# TapClip_v2.net
KiCad netlist of a schematic drawn in EAGLE
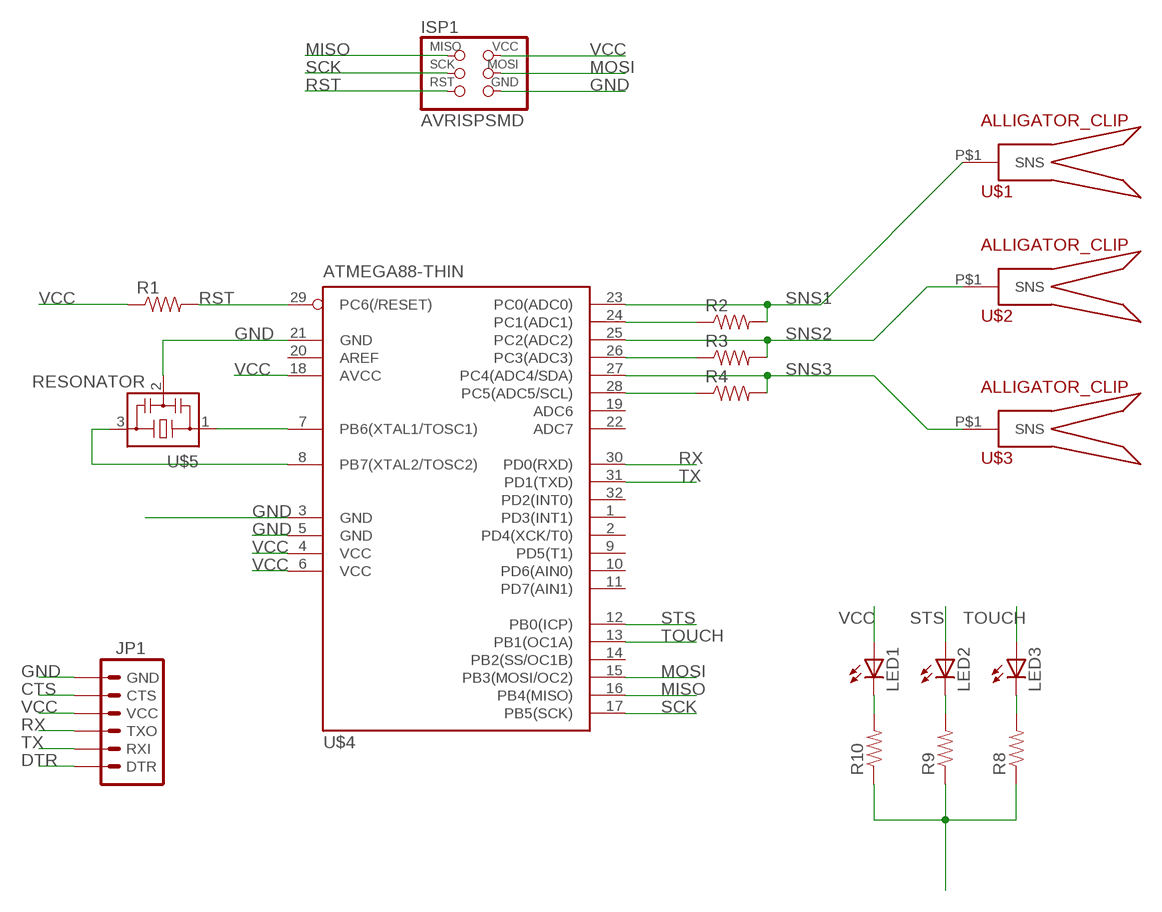
[diagram p0: schematic, sheet 1]

(export (version "E")
  (design (tool "Eeschema 10.0.6"))
  (components
    (comp (ref "ISP1")
      (value "AVRISPSMD")
      (footprint "eagle-import:2X03SMD")
      (libsource (lib "eagle-import") (part "AVRISPSMD"))
    )
    (comp (ref "JP1")
      (value "ARDUINO_SERIAL_PROGRAMSMD")
      (footprint "eagle-import:1X06-SMD")
      (libsource (lib "eagle-import") (part "ARDUINO_SERIAL_PROGRAMSMD"))
    )
    (comp (ref "LED1")
      (value "LED1206")
      (footprint "eagle-import:LED-1206")
      (libsource (lib "eagle-import") (part "LED1206"))
    )
    (comp (ref "LED2")
      (value "LED1206")
      (footprint "eagle-import:LED-1206")
      (libsource (lib "eagle-import") (part "LED1206"))
    )
    (comp (ref "LED3")
      (value "LED1206")
      (footprint "eagle-import:LED-1206")
      (libsource (lib "eagle-import") (part "LED1206"))
    )
    (comp (ref "R1")
      (value "RESISTOR0603-RES")
      (footprint "eagle-import:0603-RES")
      (libsource (lib "eagle-import") (part "RESISTOR0603-RES"))
    )
    (comp (ref "R2")
      (value "RESISTOR0603-RES")
      (footprint "eagle-import:0603-RES")
      (libsource (lib "eagle-import") (part "RESISTOR0603-RES"))
    )
    (comp (ref "R3")
      (value "RESISTOR0603-RES")
      (footprint "eagle-import:0603-RES")
      (libsource (lib "eagle-import") (part "RESISTOR0603-RES"))
    )
    (comp (ref "R4")
      (value "RESISTOR0603-RES")
      (footprint "eagle-import:0603-RES")
      (libsource (lib "eagle-import") (part "RESISTOR0603-RES"))
    )
    (comp (ref "R8")
      (value "RESISTOR1206")
      (footprint "eagle-import:1206")
      (libsource (lib "eagle-import") (part "RESISTOR1206"))
    )
    (comp (ref "R9")
      (value "RESISTOR1206")
      (footprint "eagle-import:1206")
      (libsource (lib "eagle-import") (part "RESISTOR1206"))
    )
    (comp (ref "R10")
      (value "RESISTOR1206")
      (footprint "eagle-import:1206")
      (libsource (lib "eagle-import") (part "RESISTOR1206"))
    )
    (comp (ref "U$1")
      (value "ALLIGATOR_CLIP")
      (footprint "eagle-import:ALLIGATOR_CLIP")
      (libsource (lib "eagle-import") (part "ALLIGATOR_CLIP"))
    )
    (comp (ref "U$2")
      (value "ALLIGATOR_CLIP")
      (footprint "eagle-import:ALLIGATOR_CLIP")
      (libsource (lib "eagle-import") (part "ALLIGATOR_CLIP"))
    )
    (comp (ref "U$3")
      (value "ALLIGATOR_CLIP")
      (footprint "eagle-import:ALLIGATOR_CLIP")
      (libsource (lib "eagle-import") (part "ALLIGATOR_CLIP"))
    )
    (comp (ref "U$4")
      (value "ATMEGA88-THIN")
      (footprint "eagle-import:TQFP32-08THIN")
      (libsource (lib "eagle-import") (part "ATMEGA88-THIN"))
    )
    (comp (ref "U$5")
      (value "RESONATOR")
      (footprint "eagle-import:EFOBM")
      (libsource (lib "eagle-import") (part "RESONATOR"))
    )
  )
  (nets
    (net (code "1") (name "/CTS") (class "Default")
      (node (ref "JP1") (pin "5") (pinfunction "CTS_5") (pintype "passive"))
    )
    (net (code "2") (name "/DTR") (class "Default")
      (node (ref "JP1") (pin "1") (pinfunction "DTR_1") (pintype "passive"))
    )
    (net (code "3") (name "/GND") (class "Default")
      (node (ref "ISP1") (pin "6") (pinfunction "GND_6") (pintype "passive"))
      (node (ref "JP1") (pin "6") (pinfunction "GND_6") (pintype "passive"))
      (node (ref "R10") (pin "1") (pinfunction "1_1") (pintype "passive"))
      (node (ref "R8") (pin "1") (pinfunction "1_1") (pintype "passive"))
      (node (ref "R9") (pin "1") (pinfunction "1_1") (pintype "passive"))
      (node (ref "U$4") (pin "21") (pinfunction "GND_21") (pintype "power_in"))
      (node (ref "U$4") (pin "3") (pinfunction "GND_3") (pintype "power_in"))
      (node (ref "U$4") (pin "5") (pinfunction "GND_5") (pintype "power_in"))
      (node (ref "U$5") (pin "2") (pinfunction "2_2") (pintype "passive"))
    )
    (net (code "4") (name "/MISO") (class "Default")
      (node (ref "ISP1") (pin "1") (pinfunction "MISO_1") (pintype "passive"))
      (node (ref "U$4") (pin "16") (pinfunction "PB4(MISO)_16") (pintype "bidirectional"))
    )
    (net (code "5") (name "/MOSI") (class "Default")
      (node (ref "ISP1") (pin "4") (pinfunction "MOSI_4") (pintype "passive"))
      (node (ref "U$4") (pin "15") (pinfunction "PB3(MOSI/OC2)_15") (pintype "bidirectional"))
    )
    (net (code "6") (name "/RST") (class "Default")
      (node (ref "ISP1") (pin "5") (pinfunction "RST_5") (pintype "passive"))
      (node (ref "R1") (pin "2") (pinfunction "2_2") (pintype "passive"))
      (node (ref "U$4") (pin "29") (pinfunction "PC6(/RESET)_29") (pintype "bidirectional"))
    )
    (net (code "7") (name "/RX") (class "Default")
      (node (ref "JP1") (pin "3") (pinfunction "TXO_3") (pintype "passive"))
      (node (ref "U$4") (pin "30") (pinfunction "PD0(RXD)_30") (pintype "bidirectional"))
    )
    (net (code "8") (name "/SCK") (class "Default")
      (node (ref "ISP1") (pin "3") (pinfunction "SCK_3") (pintype "passive"))
      (node (ref "U$4") (pin "17") (pinfunction "PB5(SCK)_17") (pintype "bidirectional"))
    )
    (net (code "9") (name "/SNS1") (class "Default")
      (node (ref "R2") (pin "2") (pinfunction "2_2") (pintype "passive"))
      (node (ref "U$1") (pin "P$1") (pinfunction "SNS_P$1") (pintype "bidirectional"))
      (node (ref "U$4") (pin "23") (pinfunction "PC0(ADC0)_23") (pintype "bidirectional"))
    )
    (net (code "10") (name "/SNS2") (class "Default")
      (node (ref "R3") (pin "2") (pinfunction "2_2") (pintype "passive"))
      (node (ref "U$2") (pin "P$1") (pinfunction "SNS_P$1") (pintype "bidirectional"))
      (node (ref "U$4") (pin "25") (pinfunction "PC2(ADC2)_25") (pintype "bidirectional"))
    )
    (net (code "11") (name "/SNS3") (class "Default")
      (node (ref "R4") (pin "2") (pinfunction "2_2") (pintype "passive"))
      (node (ref "U$3") (pin "P$1") (pinfunction "SNS_P$1") (pintype "bidirectional"))
      (node (ref "U$4") (pin "27") (pinfunction "PC4(ADC4/SDA)_27") (pintype "bidirectional"))
    )
    (net (code "12") (name "/STS") (class "Default")
      (node (ref "LED2") (pin "A") (pinfunction "A_A") (pintype "passive"))
      (node (ref "U$4") (pin "12") (pinfunction "PB0(ICP)_12") (pintype "bidirectional"))
    )
    (net (code "13") (name "/TOUCH") (class "Default")
      (node (ref "LED3") (pin "A") (pinfunction "A_A") (pintype "passive"))
      (node (ref "U$4") (pin "13") (pinfunction "PB1(OC1A)_13") (pintype "bidirectional"))
    )
    (net (code "14") (name "/TX") (class "Default")
      (node (ref "JP1") (pin "2") (pinfunction "RXI_2") (pintype "passive"))
      (node (ref "U$4") (pin "31") (pinfunction "PD1(TXD)_31") (pintype "bidirectional"))
    )
    (net (code "15") (name "/VCC") (class "Default")
      (node (ref "ISP1") (pin "2") (pinfunction "VCC_2") (pintype "passive"))
      (node (ref "JP1") (pin "4") (pinfunction "VCC_4") (pintype "passive"))
      (node (ref "LED1") (pin "A") (pinfunction "A_A") (pintype "passive"))
      (node (ref "R1") (pin "1") (pinfunction "1_1") (pintype "passive"))
      (node (ref "U$4") (pin "18") (pinfunction "AVCC_18") (pintype "power_in"))
      (node (ref "U$4") (pin "4") (pinfunction "VCC_4") (pintype "power_in"))
      (node (ref "U$4") (pin "6") (pinfunction "VCC_6") (pintype "power_in"))
    )
    (net (code "16") (name "Net-(LED1-PadC)") (class "Default")
      (node (ref "LED1") (pin "C") (pinfunction "C_C") (pintype "passive"))
      (node (ref "R10") (pin "2") (pinfunction "2_2") (pintype "passive"))
    )
    (net (code "17") (name "Net-(LED2-PadC)") (class "Default")
      (node (ref "LED2") (pin "C") (pinfunction "C_C") (pintype "passive"))
      (node (ref "R9") (pin "2") (pinfunction "2_2") (pintype "passive"))
    )
    (net (code "18") (name "Net-(LED3-PadC)") (class "Default")
      (node (ref "LED3") (pin "C") (pinfunction "C_C") (pintype "passive"))
      (node (ref "R8") (pin "2") (pinfunction "2_2") (pintype "passive"))
    )
    (net (code "19") (name "Net-(U$4-PB6(XTAL1{slash}TOSC1))") (class "Default")
      (node (ref "U$4") (pin "7") (pinfunction "PB6(XTAL1/TOSC1)_7") (pintype "bidirectional"))
      (node (ref "U$5") (pin "1") (pinfunction "1_1") (pintype "passive"))
    )
    (net (code "20") (name "Net-(U$4-PB7(XTAL2{slash}TOSC2))") (class "Default")
      (node (ref "U$4") (pin "8") (pinfunction "PB7(XTAL2/TOSC2)_8") (pintype "bidirectional"))
      (node (ref "U$5") (pin "3") (pinfunction "3_3") (pintype "passive"))
    )
    (net (code "21") (name "Net-(U$4-PC1(ADC1))") (class "Default")
      (node (ref "R2") (pin "1") (pinfunction "1_1") (pintype "passive"))
      (node (ref "U$4") (pin "24") (pinfunction "PC1(ADC1)_24") (pintype "bidirectional"))
    )
    (net (code "22") (name "Net-(U$4-PC3(ADC3))") (class "Default")
      (node (ref "R3") (pin "1") (pinfunction "1_1") (pintype "passive"))
      (node (ref "U$4") (pin "26") (pinfunction "PC3(ADC3)_26") (pintype "bidirectional"))
    )
    (net (code "23") (name "Net-(U$4-PC5(ADC5{slash}SCL))") (class "Default")
      (node (ref "R4") (pin "1") (pinfunction "1_1") (pintype "passive"))
      (node (ref "U$4") (pin "28") (pinfunction "PC5(ADC5/SCL)_28") (pintype "bidirectional"))
    )
    (net (code "24") (name "unconnected-(U$4-ADC6-Pad19)") (class "Default")
      (node (ref "U$4") (pin "19") (pinfunction "ADC6_19") (pintype "bidirectional"))
    )
    (net (code "25") (name "unconnected-(U$4-ADC7-Pad22)") (class "Default")
      (node (ref "U$4") (pin "22") (pinfunction "ADC7_22") (pintype "bidirectional"))
    )
    (net (code "26") (name "unconnected-(U$4-AREF-Pad20)") (class "Default")
      (node (ref "U$4") (pin "20") (pinfunction "AREF_20") (pintype "passive"))
    )
    (net (code "27") (name "unconnected-(U$4-PB2(SS{slash}OC1B)-Pad14)") (class "Default")
      (node (ref "U$4") (pin "14") (pinfunction "PB2(SS/OC1B)_14") (pintype "bidirectional"))
    )
    (net (code "28") (name "unconnected-(U$4-PD2(INT0)-Pad32)") (class "Default")
      (node (ref "U$4") (pin "32") (pinfunction "PD2(INT0)_32") (pintype "bidirectional"))
    )
    (net (code "29") (name "unconnected-(U$4-PD3(INT1)-Pad1)") (class "Default")
      (node (ref "U$4") (pin "1") (pinfunction "PD3(INT1)_1") (pintype "bidirectional"))
    )
    (net (code "30") (name "unconnected-(U$4-PD4(XCK{slash}T0)-Pad2)") (class "Default")
      (node (ref "U$4") (pin "2") (pinfunction "PD4(XCK/T0)_2") (pintype "bidirectional"))
    )
    (net (code "31") (name "unconnected-(U$4-PD5(T1)-Pad9)") (class "Default")
      (node (ref "U$4") (pin "9") (pinfunction "PD5(T1)_9") (pintype "bidirectional"))
    )
    (net (code "32") (name "unconnected-(U$4-PD6(AIN0)-Pad10)") (class "Default")
      (node (ref "U$4") (pin "10") (pinfunction "PD6(AIN0)_10") (pintype "bidirectional"))
    )
    (net (code "33") (name "unconnected-(U$4-PD7(AIN1)-Pad11)") (class "Default")
      (node (ref "U$4") (pin "11") (pinfunction "PD7(AIN1)_11") (pintype "bidirectional"))
    )
  )
)
